# power_board.net
KiCad netlist of a schematic drawn in EAGLE
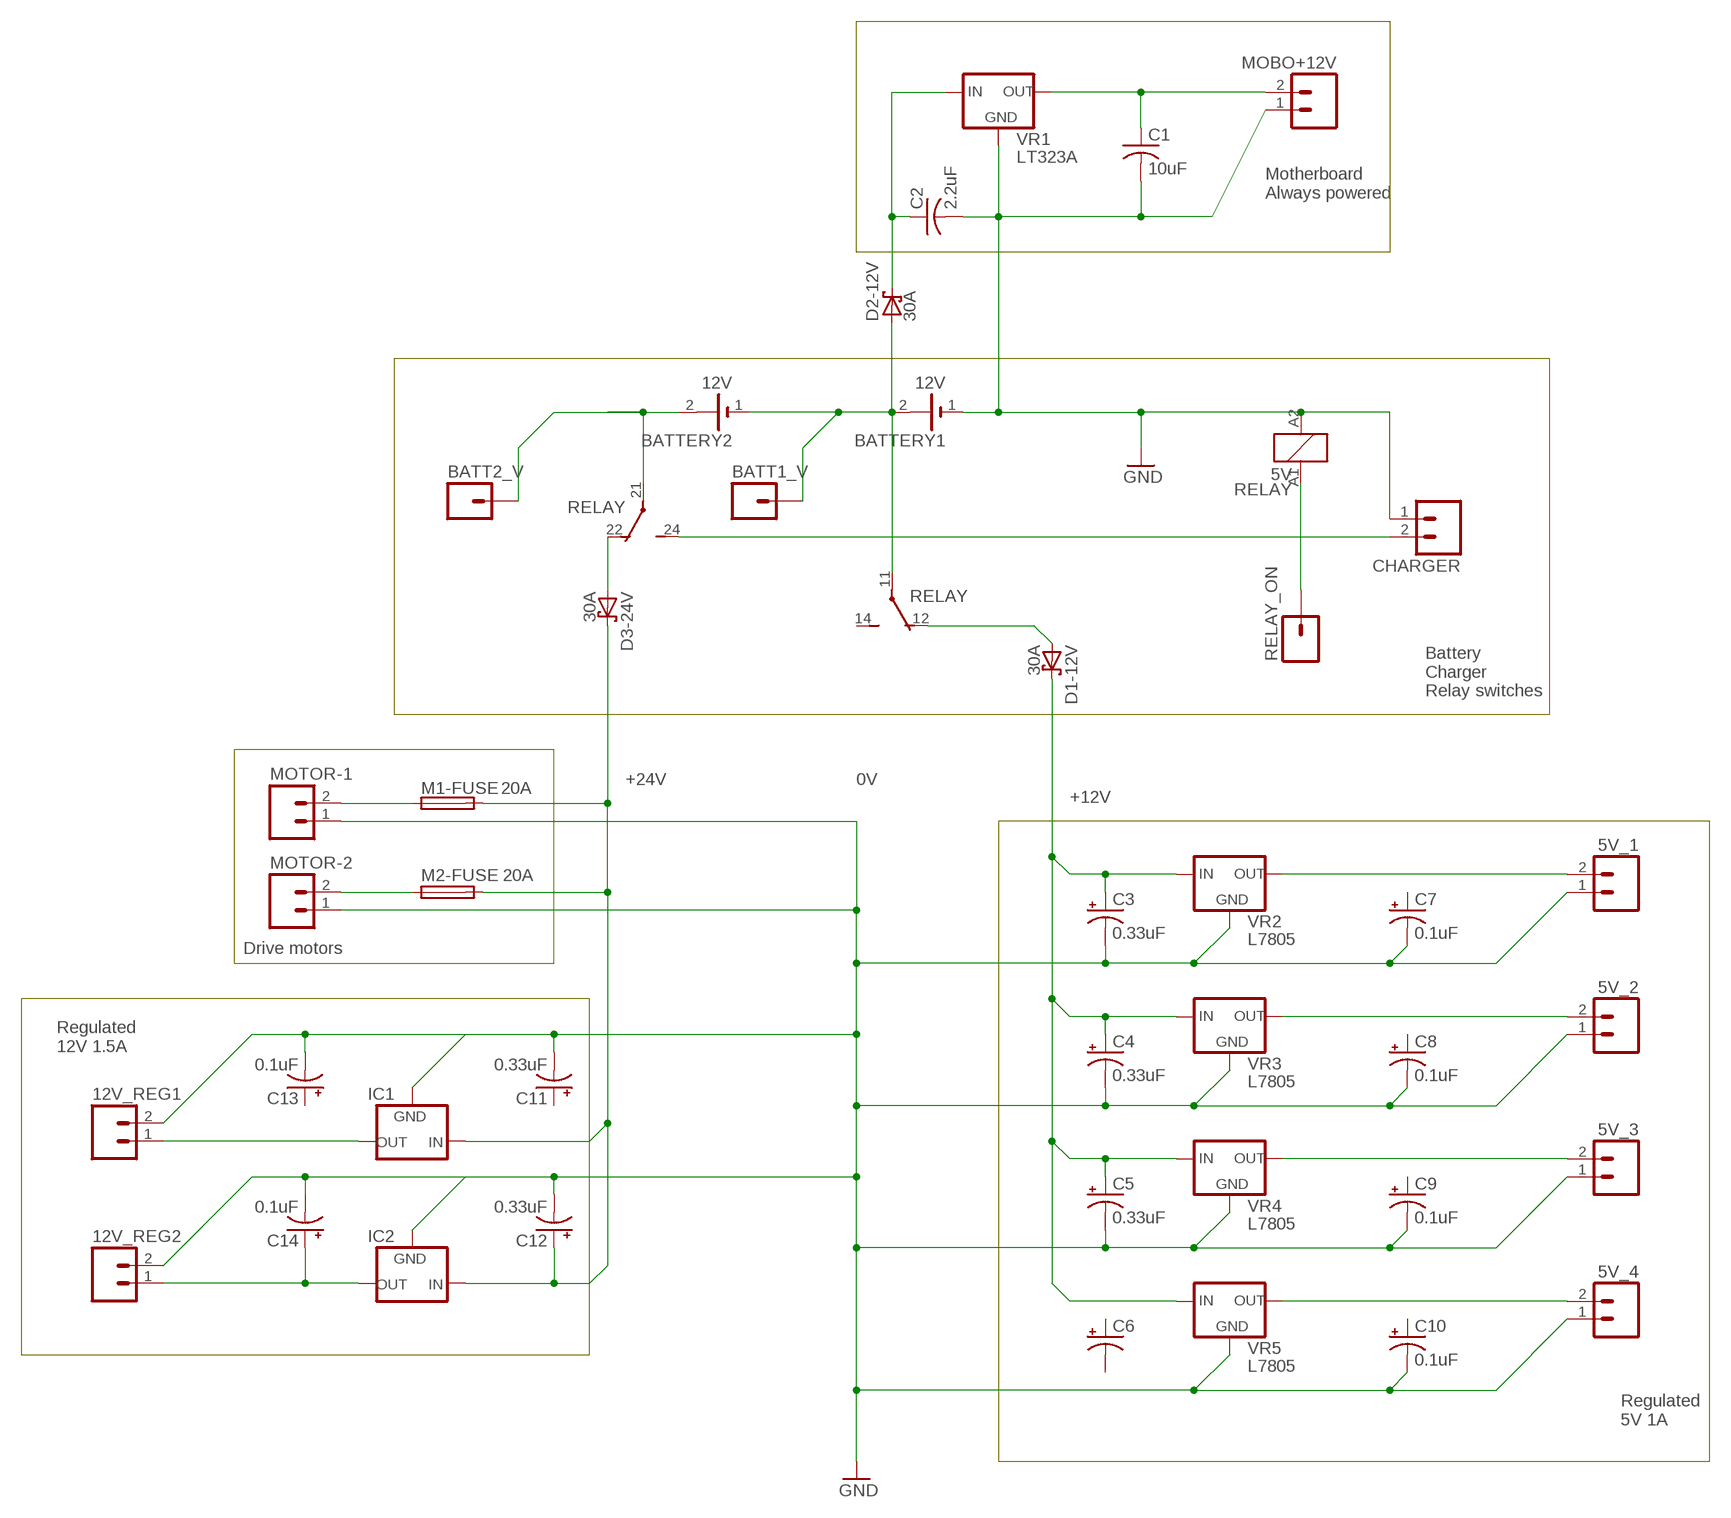
[diagram p0: schematic, sheet 1]

(export (version "E")
  (design (tool "Eeschema 10.0.6"))
  (components
    (comp (ref "5V_1")
      (value "2-HOLESSC3.81MM")
      (footprint "eagle-import:SCREWTERMINAL-3.81MM")
      (libsource (lib "eagle-import") (part "2-HOLESSC3.81MM"))
    )
    (comp (ref "5V_2")
      (value "2-HOLESSC3.81MM")
      (footprint "eagle-import:SCREWTERMINAL-3.81MM")
      (libsource (lib "eagle-import") (part "2-HOLESSC3.81MM"))
    )
    (comp (ref "5V_3")
      (value "2-HOLESSC3.81MM")
      (footprint "eagle-import:SCREWTERMINAL-3.81MM")
      (libsource (lib "eagle-import") (part "2-HOLESSC3.81MM"))
    )
    (comp (ref "5V_4")
      (value "2-HOLESSC3.81MM")
      (footprint "eagle-import:SCREWTERMINAL-3.81MM")
      (libsource (lib "eagle-import") (part "2-HOLESSC3.81MM"))
    )
    (comp (ref "12V_REG1")
      (value "2-HOLESSC3.81MM")
      (footprint "eagle-import:SCREWTERMINAL-3.81MM")
      (libsource (lib "eagle-import") (part "2-HOLESSC3.81MM"))
    )
    (comp (ref "12V_REG2")
      (value "2-HOLESSC3.81MM")
      (footprint "eagle-import:SCREWTERMINAL-3.81MM")
      (libsource (lib "eagle-import") (part "2-HOLESSC3.81MM"))
    )
    (comp (ref "BATT1_V")
      (value "1-HOLE")
      (footprint "eagle-import:1-HOLE_BIG")
      (libsource (lib "eagle-import") (part "1-HOLE"))
    )
    (comp (ref "BATT2_V")
      (value "1-HOLE")
      (footprint "eagle-import:1-HOLE_BIG")
      (libsource (lib "eagle-import") (part "1-HOLE"))
    )
    (comp (ref "BATTERY1")
      (value "12V")
      (footprint "eagle-import:SCREWTERMINAL-5MM")
      (libsource (lib "eagle-import") (part "BATTERY-ST"))
    )
    (comp (ref "BATTERY2")
      (value "12V")
      (footprint "eagle-import:SCREWTERMINAL-5MM")
      (libsource (lib "eagle-import") (part "BATTERY-ST"))
    )
    (comp (ref "C1")
      (value "10uF")
      (footprint "eagle-import:C050-024X044")
      (libsource (lib "eagle-import") (part "CAPACITOR"))
    )
    (comp (ref "C2")
      (value "2.2uF")
      (footprint "eagle-import:C050-024X044")
      (libsource (lib "eagle-import") (part "CAPACITOR"))
    )
    (comp (ref "C3")
      (value "0.33uF")
      (footprint "eagle-import:E2,5-5")
      (libsource (lib "eagle-import") (part "CAPACITOR_POL"))
    )
    (comp (ref "C4")
      (value "0.33uF")
      (footprint "eagle-import:E2,5-5")
      (libsource (lib "eagle-import") (part "CAPACITOR_POL"))
    )
    (comp (ref "C5")
      (value "0.33uF")
      (footprint "eagle-import:E2,5-5")
      (libsource (lib "eagle-import") (part "CAPACITOR_POL"))
    )
    (comp (ref "C6")
      (value "CAPACITOR_POL")
      (footprint "eagle-import:E2,5-5")
      (libsource (lib "eagle-import") (part "CAPACITOR_POL"))
    )
    (comp (ref "C7")
      (value "0.1uF")
      (footprint "eagle-import:E2,5-5")
      (libsource (lib "eagle-import") (part "CAPACITOR_POL"))
    )
    (comp (ref "C8")
      (value "0.1uF")
      (footprint "eagle-import:E2,5-5")
      (libsource (lib "eagle-import") (part "CAPACITOR_POL"))
    )
    (comp (ref "C9")
      (value "0.1uF")
      (footprint "eagle-import:E2,5-5")
      (libsource (lib "eagle-import") (part "CAPACITOR_POL"))
    )
    (comp (ref "C10")
      (value "0.1uF")
      (footprint "eagle-import:E2,5-5")
      (libsource (lib "eagle-import") (part "CAPACITOR_POL"))
    )
    (comp (ref "C11")
      (value "0.33uF")
      (footprint "eagle-import:E2,5-5")
      (libsource (lib "eagle-import") (part "CAPACITOR_POL"))
    )
    (comp (ref "C12")
      (value "0.33uF")
      (footprint "eagle-import:E2,5-5")
      (libsource (lib "eagle-import") (part "CAPACITOR_POL"))
    )
    (comp (ref "C13")
      (value "0.1uF")
      (footprint "eagle-import:E2,5-5")
      (libsource (lib "eagle-import") (part "CAPACITOR_POL"))
    )
    (comp (ref "C14")
      (value "0.1uF")
      (footprint "eagle-import:E2,5-5")
      (libsource (lib "eagle-import") (part "CAPACITOR_POL"))
    )
    (comp (ref "CHARGER")
      (value "24V")
      (footprint "eagle-import:SCREWTERMINAL-5MM")
      (libsource (lib "eagle-import") (part "2-HOLESSC5MM"))
    )
    (comp (ref "D1-12V")
      (value "30A")
      (footprint "eagle-import:TO22-DIODE-H")
      (libsource (lib "eagle-import") (part "NTST30100SG-H"))
    )
    (comp (ref "D2-12V")
      (value "30A")
      (footprint "eagle-import:TO22-DIODE-H")
      (libsource (lib "eagle-import") (part "NTST30100SG-H"))
    )
    (comp (ref "D3-24V")
      (value "30A")
      (footprint "eagle-import:TO22-DIODE-H")
      (libsource (lib "eagle-import") (part "NTST30100SG-H"))
    )
    (comp (ref "IC1")
      (value "L7812CD2T-TRTO-263")
      (footprint "eagle-import:TO263")
      (libsource (lib "eagle-import") (part "L7812CD2T-TRTO-263"))
    )
    (comp (ref "IC2")
      (value "L7812CD2T-TRTO-263")
      (footprint "eagle-import:TO263")
      (libsource (lib "eagle-import") (part "L7812CD2T-TRTO-263"))
    )
    (comp (ref "M1-FUSE")
      (value "20A")
      (footprint "eagle-import:FUSE-5X20MM_SMD")
      (libsource (lib "eagle-import") (part "FUSE"))
    )
    (comp (ref "M2-FUSE")
      (value "20A")
      (footprint "eagle-import:FUSE-5X20MM_SMD")
      (libsource (lib "eagle-import") (part "FUSE"))
    )
    (comp (ref "MOBO+12V")
      (value "2-HOLESSC3.81MM")
      (footprint "eagle-import:SCREWTERMINAL-3.81MM")
      (libsource (lib "eagle-import") (part "2-HOLESSC3.81MM"))
    )
    (comp (ref "MOTOR-1")
      (value "2-HOLESSC5MM")
      (footprint "eagle-import:SCREWTERMINAL-5MM")
      (libsource (lib "eagle-import") (part "2-HOLESSC5MM"))
    )
    (comp (ref "MOTOR-2")
      (value "2-HOLESSC5MM")
      (footprint "eagle-import:SCREWTERMINAL-5MM")
      (libsource (lib "eagle-import") (part "2-HOLESSC5MM"))
    )
    (comp (ref "RELAY")
      (value "5V")
      (footprint "eagle-import:RELAY_RT2")
      (fields (field (name "MPN") "RT424A05"))
      (libsource (lib "eagle-import") (part "RT424A05"))
    )
    (comp (ref "RELAY_ON")
      (value "1-HOLE\"")
      (footprint "eagle-import:1-HOLE")
      (libsource (lib "eagle-import") (part "1-HOLE{dblquote}"))
    )
    (comp (ref "VR1")
      (value "LT323A")
      (footprint "eagle-import:TO220V")
      (libsource (lib "eagle-import") (part "LT323AT-V"))
    )
    (comp (ref "VR2")
      (value "L7805")
      (footprint "eagle-import:TO263")
      (libsource (lib "eagle-import") (part "L7805ACD2T-TR"))
    )
    (comp (ref "VR3")
      (value "L7805")
      (footprint "eagle-import:TO263")
      (libsource (lib "eagle-import") (part "L7805ACD2T-TR"))
    )
    (comp (ref "VR4")
      (value "L7805")
      (footprint "eagle-import:TO263")
      (libsource (lib "eagle-import") (part "L7805ACD2T-TR"))
    )
    (comp (ref "VR5")
      (value "L7805")
      (footprint "eagle-import:TO263")
      (libsource (lib "eagle-import") (part "L7805ACD2T-TR"))
    )
  )
  (nets
    (net (code "1") (name "GND") (class "Default")
      (node (ref "12V_REG1") (pin "2") (pinfunction "2_2") (pintype "passive"))
      (node (ref "12V_REG2") (pin "2") (pinfunction "2_2") (pintype "passive"))
      (node (ref "5V_1") (pin "1") (pinfunction "1_1") (pintype "passive"))
      (node (ref "5V_2") (pin "1") (pinfunction "1_1") (pintype "passive"))
      (node (ref "5V_3") (pin "1") (pinfunction "1_1") (pintype "passive"))
      (node (ref "5V_4") (pin "1") (pinfunction "1_1") (pintype "passive"))
      (node (ref "BATTERY1") (pin "1") (pinfunction "-_1") (pintype "passive"))
      (node (ref "C1") (pin "2") (pinfunction "2_2") (pintype "passive"))
      (node (ref "C10") (pin "-") (pinfunction "-_-") (pintype "passive"))
      (node (ref "C11") (pin "-") (pinfunction "-_-") (pintype "passive"))
      (node (ref "C12") (pin "-") (pinfunction "-_-") (pintype "passive"))
      (node (ref "C13") (pin "-") (pinfunction "-_-") (pintype "passive"))
      (node (ref "C14") (pin "-") (pinfunction "-_-") (pintype "passive"))
      (node (ref "C2") (pin "2") (pinfunction "2_2") (pintype "passive"))
      (node (ref "C3") (pin "-") (pinfunction "-_-") (pintype "passive"))
      (node (ref "C4") (pin "-") (pinfunction "-_-") (pintype "passive"))
      (node (ref "C5") (pin "-") (pinfunction "-_-") (pintype "passive"))
      (node (ref "C7") (pin "-") (pinfunction "-_-") (pintype "passive"))
      (node (ref "C8") (pin "-") (pinfunction "-_-") (pintype "passive"))
      (node (ref "C9") (pin "-") (pinfunction "-_-") (pintype "passive"))
      (node (ref "CHARGER") (pin "1") (pinfunction "1_1") (pintype "passive"))
      (node (ref "IC1") (pin "3") (pinfunction "GND_3") (pintype "input"))
      (node (ref "IC2") (pin "3") (pinfunction "GND_3") (pintype "input"))
      (node (ref "MOBO+12V") (pin "1") (pinfunction "1_1") (pintype "passive"))
      (node (ref "MOTOR-1") (pin "1") (pinfunction "1_1") (pintype "passive"))
      (node (ref "MOTOR-2") (pin "1") (pinfunction "1_1") (pintype "passive"))
      (node (ref "RELAY") (pin "A2") (pinfunction "2_A2") (pintype "passive"))
      (node (ref "VR1") (pin "2") (pinfunction "GND_2") (pintype "input"))
      (node (ref "VR2") (pin "3") (pinfunction "GND_3") (pintype "input"))
      (node (ref "VR3") (pin "3") (pinfunction "GND_3") (pintype "input"))
      (node (ref "VR4") (pin "3") (pinfunction "GND_3") (pintype "input"))
      (node (ref "VR5") (pin "3") (pinfunction "GND_3") (pintype "input"))
    )
    (net (code "2") (name "Net-(BATT1_V-1)") (class "Default")
      (node (ref "BATT1_V") (pin "P$1") (pinfunction "1_P$1") (pintype "passive"))
      (node (ref "BATTERY1") (pin "2") (pinfunction "+_2") (pintype "passive"))
      (node (ref "BATTERY2") (pin "1") (pinfunction "-_1") (pintype "passive"))
      (node (ref "D2-12V") (pin "P$1") (pinfunction "A_P$1") (pintype "passive"))
      (node (ref "RELAY") (pin "11") (pinfunction "P_11") (pintype "passive"))
    )
    (net (code "3") (name "Net-(BATT2_V-1)") (class "Default")
      (node (ref "BATT2_V") (pin "P$1") (pinfunction "1_P$1") (pintype "passive"))
      (node (ref "BATTERY2") (pin "2") (pinfunction "+_2") (pintype "passive"))
      (node (ref "RELAY") (pin "21") (pinfunction "P_21") (pintype "passive"))
    )
    (net (code "4") (name "Net-(D1-12V-A)") (class "Default")
      (node (ref "D1-12V") (pin "P$1") (pinfunction "A_P$1") (pintype "passive"))
      (node (ref "RELAY") (pin "12") (pinfunction "O_12") (pintype "passive"))
    )
    (net (code "5") (name "Net-(D1-12V-C)") (class "Default")
      (node (ref "C3") (pin "+") (pinfunction "+_+") (pintype "passive"))
      (node (ref "C4") (pin "+") (pinfunction "+_+") (pintype "passive"))
      (node (ref "C5") (pin "+") (pinfunction "+_+") (pintype "passive"))
      (node (ref "D1-12V") (pin "P$2") (pinfunction "C_P$2") (pintype "passive"))
      (node (ref "VR2") (pin "1") (pinfunction "IN_1") (pintype "input"))
      (node (ref "VR3") (pin "1") (pinfunction "IN_1") (pintype "input"))
      (node (ref "VR4") (pin "1") (pinfunction "IN_1") (pintype "input"))
      (node (ref "VR5") (pin "1") (pinfunction "IN_1") (pintype "input"))
    )
    (net (code "6") (name "Net-(D2-12V-C)") (class "Default")
      (node (ref "C2") (pin "1") (pinfunction "1_1") (pintype "passive"))
      (node (ref "D2-12V") (pin "P$2") (pinfunction "C_P$2") (pintype "passive"))
      (node (ref "VR1") (pin "1") (pinfunction "IN_1") (pintype "input"))
    )
    (net (code "7") (name "Net-(D3-24V-A)") (class "Default")
      (node (ref "D3-24V") (pin "P$1") (pinfunction "A_P$1") (pintype "passive"))
      (node (ref "RELAY") (pin "22") (pinfunction "O_22") (pintype "passive"))
    )
    (net (code "8") (name "Net-(D3-24V-C)") (class "Default")
      (node (ref "C12") (pin "+") (pinfunction "+_+") (pintype "passive"))
      (node (ref "D3-24V") (pin "P$2") (pinfunction "C_P$2") (pintype "passive"))
      (node (ref "IC1") (pin "1") (pinfunction "IN_1") (pintype "input"))
      (node (ref "IC2") (pin "1") (pinfunction "IN_1") (pintype "input"))
      (node (ref "M1-FUSE") (pin "P$2") (pinfunction "2_P$2") (pintype "passive"))
      (node (ref "M2-FUSE") (pin "P$2") (pinfunction "2_P$2") (pintype "passive"))
    )
    (net (code "9") (name "Net-(IC1-OUT)") (class "Default")
      (node (ref "12V_REG1") (pin "1") (pinfunction "1_1") (pintype "passive"))
      (node (ref "IC1") (pin "2") (pinfunction "OUT_2") (pintype "passive"))
    )
    (net (code "10") (name "Net-(IC2-OUT)") (class "Default")
      (node (ref "12V_REG2") (pin "1") (pinfunction "1_1") (pintype "passive"))
      (node (ref "C14") (pin "+") (pinfunction "+_+") (pintype "passive"))
      (node (ref "IC2") (pin "2") (pinfunction "OUT_2") (pintype "passive"))
    )
    (net (code "11") (name "Net-(M1-FUSE-1)") (class "Default")
      (node (ref "M1-FUSE") (pin "P$1") (pinfunction "1_P$1") (pintype "passive"))
      (node (ref "MOTOR-1") (pin "2") (pinfunction "2_2") (pintype "passive"))
    )
    (net (code "12") (name "Net-(M2-FUSE-1)") (class "Default")
      (node (ref "M2-FUSE") (pin "P$1") (pinfunction "1_P$1") (pintype "passive"))
      (node (ref "MOTOR-2") (pin "2") (pinfunction "2_2") (pintype "passive"))
    )
    (net (code "13") (name "Net-(RELAYA-1)") (class "Default")
      (node (ref "RELAY") (pin "A1") (pinfunction "1_A1") (pintype "passive"))
      (node (ref "RELAY_ON") (pin "1") (pinfunction "1_1") (pintype "passive"))
    )
    (net (code "14") (name "Net-(RELAYC-S)") (class "Default")
      (node (ref "CHARGER") (pin "2") (pinfunction "2_2") (pintype "passive"))
      (node (ref "RELAY") (pin "24") (pinfunction "S_24") (pintype "passive"))
    )
    (net (code "15") (name "Net-(VR1-OUT)") (class "Default")
      (node (ref "C1") (pin "1") (pinfunction "1_1") (pintype "passive"))
      (node (ref "MOBO+12V") (pin "2") (pinfunction "2_2") (pintype "passive"))
      (node (ref "VR1") (pin "3") (pinfunction "OUT_3") (pintype "passive"))
    )
    (net (code "16") (name "Net-(VR2-OUT)") (class "Default")
      (node (ref "5V_1") (pin "2") (pinfunction "2_2") (pintype "passive"))
      (node (ref "VR2") (pin "2") (pinfunction "OUT_2") (pintype "passive"))
    )
    (net (code "17") (name "Net-(VR3-OUT)") (class "Default")
      (node (ref "5V_2") (pin "2") (pinfunction "2_2") (pintype "passive"))
      (node (ref "VR3") (pin "2") (pinfunction "OUT_2") (pintype "passive"))
    )
    (net (code "18") (name "Net-(VR4-OUT)") (class "Default")
      (node (ref "5V_3") (pin "2") (pinfunction "2_2") (pintype "passive"))
      (node (ref "VR4") (pin "2") (pinfunction "OUT_2") (pintype "passive"))
    )
    (net (code "19") (name "Net-(VR5-OUT)") (class "Default")
      (node (ref "5V_4") (pin "2") (pinfunction "2_2") (pintype "passive"))
      (node (ref "VR5") (pin "2") (pinfunction "OUT_2") (pintype "passive"))
    )
    (net (code "20") (name "unconnected-(C6-Pad+)") (class "Default")
      (node (ref "C6") (pin "+") (pinfunction "+_+") (pintype "passive"))
    )
    (net (code "21") (name "unconnected-(C6-Pad-)") (class "Default")
      (node (ref "C6") (pin "-") (pinfunction "-_-") (pintype "passive"))
    )
    (net (code "22") (name "unconnected-(C7-Pad+)") (class "Default")
      (node (ref "C7") (pin "+") (pinfunction "+_+") (pintype "passive"))
    )
    (net (code "23") (name "unconnected-(C8-Pad+)") (class "Default")
      (node (ref "C8") (pin "+") (pinfunction "+_+") (pintype "passive"))
    )
    (net (code "24") (name "unconnected-(C9-Pad+)") (class "Default")
      (node (ref "C9") (pin "+") (pinfunction "+_+") (pintype "passive"))
    )
    (net (code "25") (name "unconnected-(C10-Pad+)") (class "Default")
      (node (ref "C10") (pin "+") (pinfunction "+_+") (pintype "passive"))
    )
    (net (code "26") (name "unconnected-(C11-Pad+)") (class "Default")
      (node (ref "C11") (pin "+") (pinfunction "+_+") (pintype "passive"))
    )
    (net (code "27") (name "unconnected-(C13-Pad+)") (class "Default")
      (node (ref "C13") (pin "+") (pinfunction "+_+") (pintype "passive"))
    )
    (net (code "28") (name "unconnected-(RELAYB-S-Pad14)") (class "Default")
      (node (ref "RELAY") (pin "14") (pinfunction "S_14") (pintype "passive"))
    )
  )
)
